# Automated_Blinds_Remote.net
KiCad netlist of a schematic drawn in EAGLE
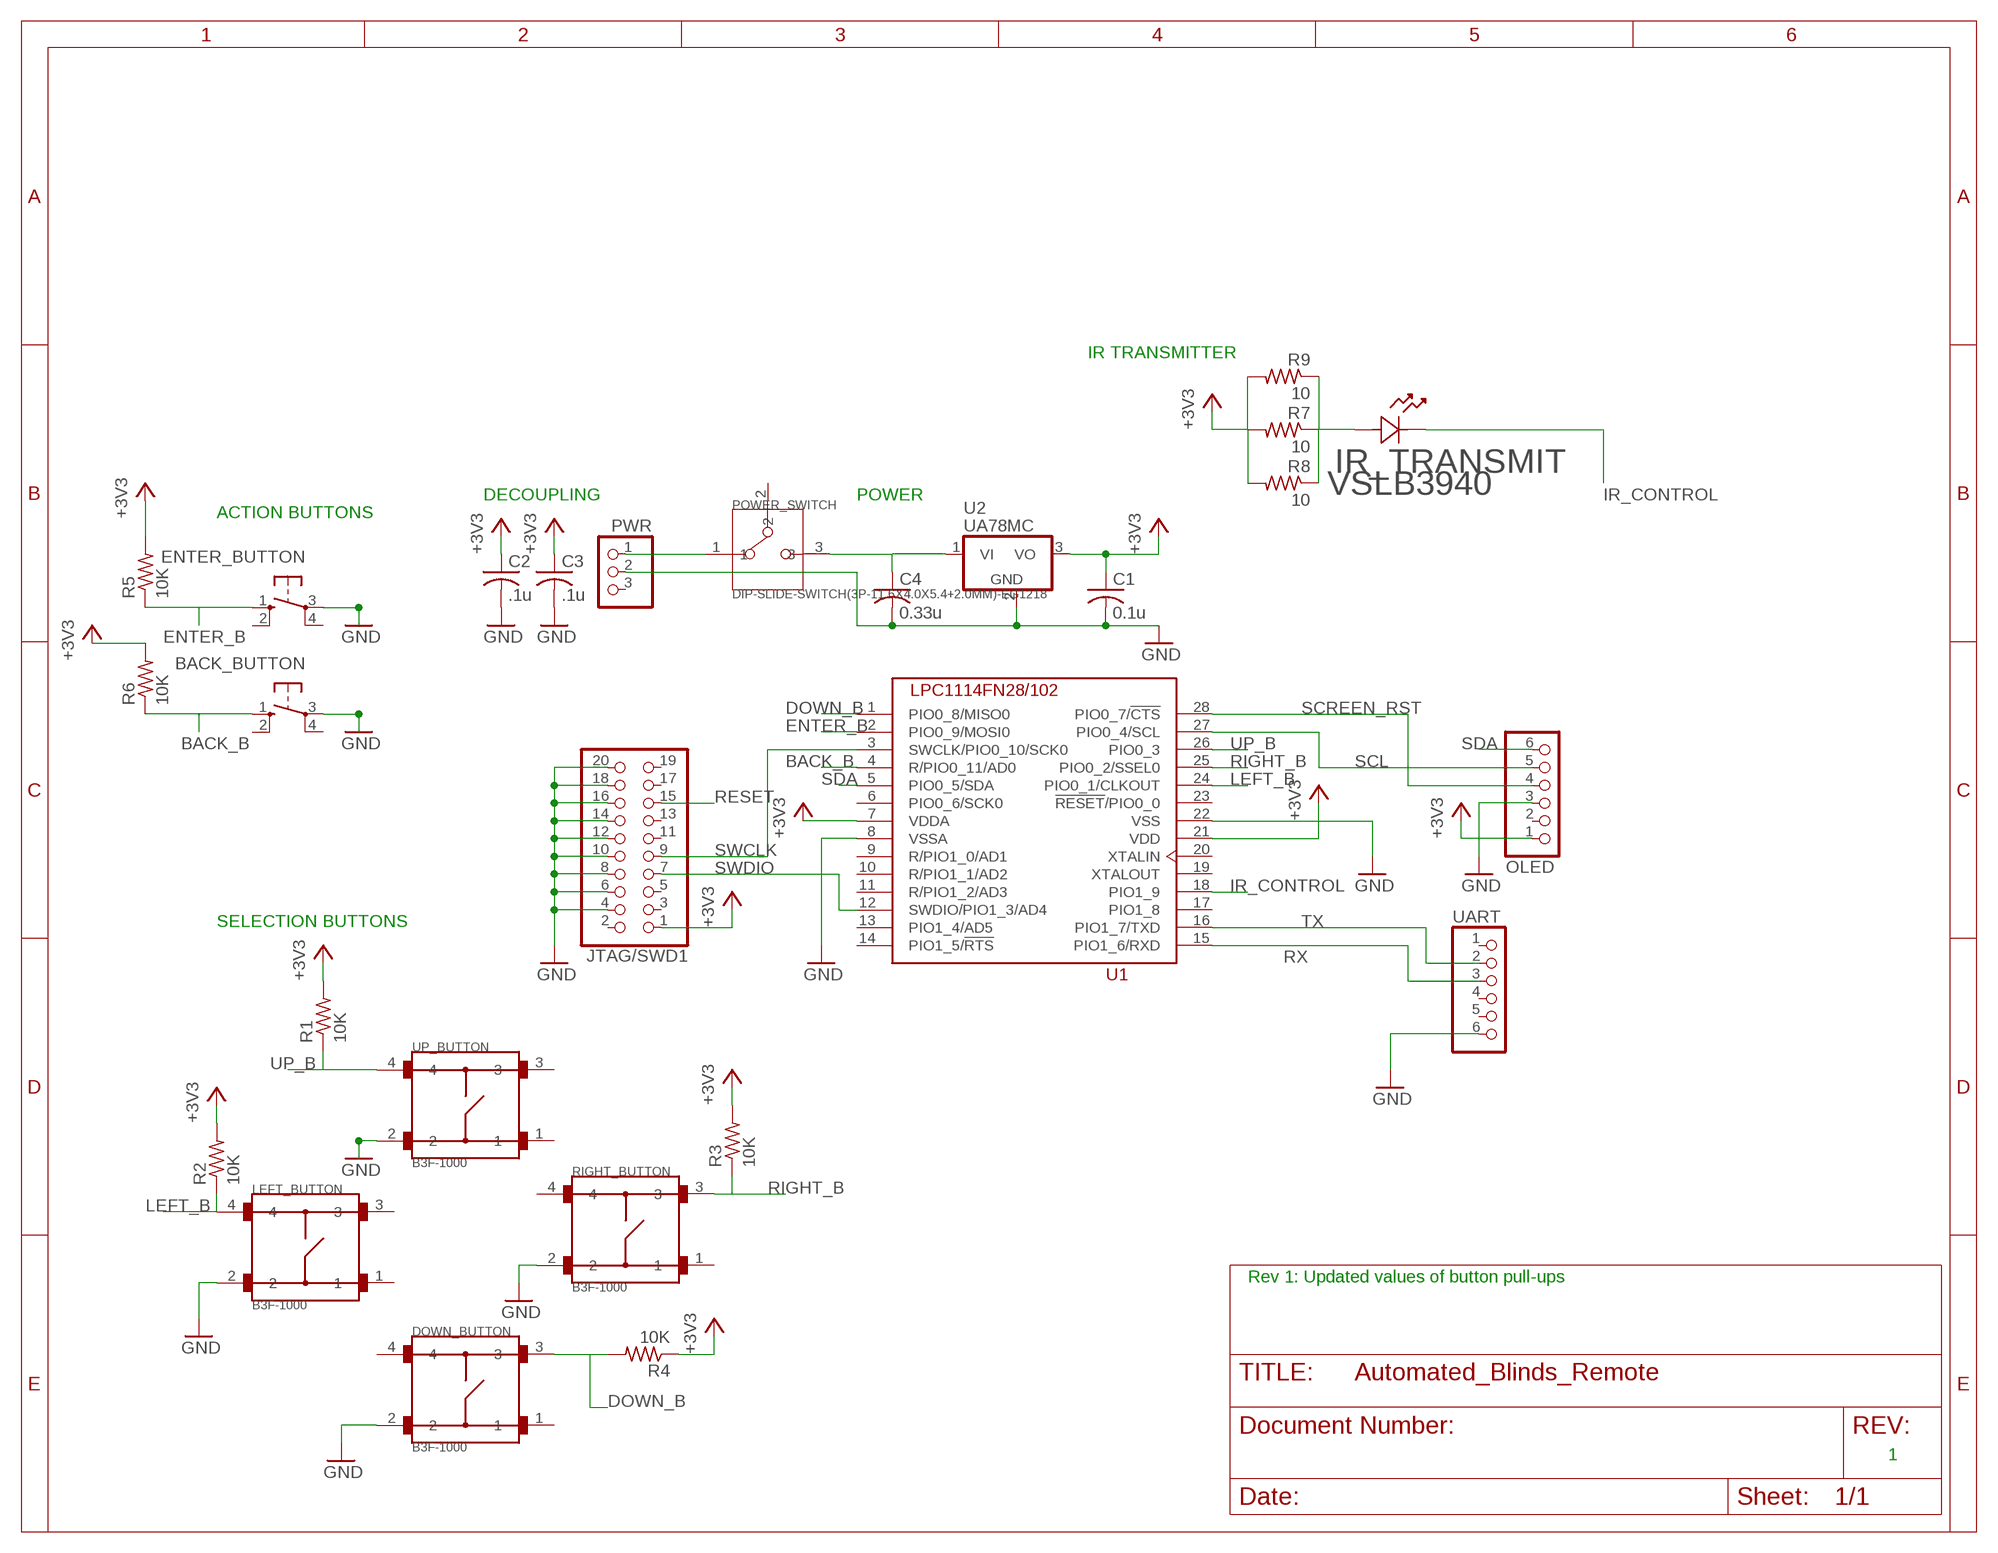
[diagram p0: schematic, sheet 1]

(export (version "E")
  (design (tool "Eeschema 10.0.6"))
  (components
    (comp (ref "BACK_BUTTON")
      (value "40/XX")
      (footprint "eagle-import:B3F_40XX")
      (libsource (lib "eagle-import") (part "40/XX"))
    )
    (comp (ref "C1")
      (value "0.1u")
      (footprint "eagle-import:C050-024X044")
      (libsource (lib "eagle-import") (part "C-US050-024X044"))
    )
    (comp (ref "C2")
      (value ".1u")
      (footprint "eagle-import:C050-024X044")
      (libsource (lib "eagle-import") (part "C-US050-024X044"))
    )
    (comp (ref "C3")
      (value ".1u")
      (footprint "eagle-import:C050-024X044")
      (libsource (lib "eagle-import") (part "C-US050-024X044"))
    )
    (comp (ref "C4")
      (value "0.33u")
      (footprint "eagle-import:C050-024X044")
      (libsource (lib "eagle-import") (part "C-US050-024X044"))
    )
    (comp (ref "DOWN_BUTTON")
      (value "B3F-1000")
      (footprint "eagle-import:SW_B3F-1000")
      (fields (field (name "MF") "Omron"))
      (libsource (lib "eagle-import") (part "B3F-1000"))
    )
    (comp (ref "ENTER_BUTTON")
      (value "40/XX")
      (footprint "eagle-import:B3F_40XX")
      (libsource (lib "eagle-import") (part "40/XX"))
    )
    (comp (ref "IR_TRANSMIT")
      (value "VSLB3940")
      (footprint "eagle-import:LED_TLH")
      (libsource (lib "eagle-import") (part "VSLB3940"))
    )
    (comp (ref "JTAG/SWD1")
      (value "PINHD-2X10")
      (footprint "eagle-import:2X10")
      (libsource (lib "eagle-import") (part "PINHD-2X10"))
    )
    (comp (ref "LEFT_BUTTON")
      (value "B3F-1000")
      (footprint "eagle-import:SW_B3F-1000")
      (fields (field (name "MF") "Omron"))
      (libsource (lib "eagle-import") (part "B3F-1000"))
    )
    (comp (ref "OLED")
      (value "PINHD-1X6")
      (footprint "eagle-import:1X06")
      (libsource (lib "eagle-import") (part "PINHD-1X6"))
    )
    (comp (ref "POWER_SWITCH")
      (value "DIP-SLIDE-SWITCH(3P-11.6X4.0X5.4+2.0MM)-EG1218")
      (footprint "eagle-import:SW3-2.5-11.6X4.0X5.4+2.0MM")
      (fields (field (name "MF") "E-Switch") (field (name "MP") "EG1218"))
      (libsource (lib "eagle-import") (part "DIP-SLIDE-SWITCH(3P-11.6X4.0X5.4+2.0MM)-EG1218"))
    )
    (comp (ref "PWR")
      (value "PINHD-1X3")
      (footprint "eagle-import:1X03")
      (libsource (lib "eagle-import") (part "PINHD-1X3"))
    )
    (comp (ref "R1")
      (value "10K")
      (footprint "eagle-import:0207_10")
      (libsource (lib "eagle-import") (part "R-US_0207/10"))
    )
    (comp (ref "R2")
      (value "10K")
      (footprint "eagle-import:0207_10")
      (libsource (lib "eagle-import") (part "R-US_0207/10"))
    )
    (comp (ref "R3")
      (value "10K")
      (footprint "eagle-import:0207_10")
      (libsource (lib "eagle-import") (part "R-US_0207/10"))
    )
    (comp (ref "R4")
      (value "10K")
      (footprint "eagle-import:0207_10")
      (libsource (lib "eagle-import") (part "R-US_0207/10"))
    )
    (comp (ref "R5")
      (value "10K")
      (footprint "eagle-import:0207_10")
      (libsource (lib "eagle-import") (part "R-US_0207/10"))
    )
    (comp (ref "R6")
      (value "10K")
      (footprint "eagle-import:0207_10")
      (libsource (lib "eagle-import") (part "R-US_0207/10"))
    )
    (comp (ref "R7")
      (value "10")
      (footprint "eagle-import:0207_10")
      (libsource (lib "eagle-import") (part "R-US_0207/10"))
    )
    (comp (ref "R8")
      (value "10")
      (footprint "eagle-import:0207_10")
      (libsource (lib "eagle-import") (part "R-US_0207/10"))
    )
    (comp (ref "R9")
      (value "10")
      (footprint "eagle-import:0207_10")
      (libsource (lib "eagle-import") (part "R-US_0207/10"))
    )
    (comp (ref "RIGHT_BUTTON")
      (value "B3F-1000")
      (footprint "eagle-import:SW_B3F-1000")
      (fields (field (name "MF") "Omron"))
      (libsource (lib "eagle-import") (part "B3F-1000"))
    )
    (comp (ref "U1")
      (value "LPC1114FN28/102")
      (footprint "eagle-import:DIL28-6")
      (libsource (lib "eagle-import") (part "LPC1114FN28/102"))
    )
    (comp (ref "U2")
      (value "UA78MC")
      (footprint "eagle-import:TO220V")
      (libsource (lib "eagle-import") (part "UA78MC"))
    )
    (comp (ref "UART")
      (value "PINHD-1X6")
      (footprint "eagle-import:1X06")
      (libsource (lib "eagle-import") (part "PINHD-1X6"))
    )
    (comp (ref "UP_BUTTON")
      (value "B3F-1000")
      (footprint "eagle-import:SW_B3F-1000")
      (fields (field (name "MF") "Omron"))
      (libsource (lib "eagle-import") (part "B3F-1000"))
    )
  )
  (nets
    (net (code "1") (name "+3V3") (class "Default")
      (node (ref "C1") (pin "1") (pinfunction "1_1") (pintype "passive"))
      (node (ref "C2") (pin "1") (pinfunction "1_1") (pintype "passive"))
      (node (ref "C3") (pin "1") (pinfunction "1_1") (pintype "passive"))
      (node (ref "JTAG/SWD1") (pin "1") (pinfunction "1_1") (pintype "passive"))
      (node (ref "OLED") (pin "1") (pinfunction "1_1") (pintype "passive"))
      (node (ref "R1") (pin "2") (pinfunction "2_2") (pintype "passive"))
      (node (ref "R2") (pin "2") (pinfunction "2_2") (pintype "passive"))
      (node (ref "R3") (pin "2") (pinfunction "2_2") (pintype "passive"))
      (node (ref "R4") (pin "1") (pinfunction "1_1") (pintype "passive"))
      (node (ref "R5") (pin "2") (pinfunction "2_2") (pintype "passive"))
      (node (ref "R6") (pin "2") (pinfunction "2_2") (pintype "passive"))
      (node (ref "R7") (pin "2") (pinfunction "2_2") (pintype "passive"))
      (node (ref "R8") (pin "2") (pinfunction "2_2") (pintype "passive"))
      (node (ref "R9") (pin "2") (pinfunction "2_2") (pintype "passive"))
      (node (ref "U1") (pin "21") (pinfunction "VDD_21") (pintype "power_in"))
      (node (ref "U1") (pin "7") (pinfunction "VDDA_7") (pintype "power_in"))
      (node (ref "U2") (pin "3") (pinfunction "VO_3") (pintype "passive"))
    )
    (net (code "2") (name "/BACK_B") (class "Default")
      (node (ref "BACK_BUTTON") (pin "1") (pinfunction "S_1") (pintype "passive"))
      (node (ref "R6") (pin "1") (pinfunction "1_1") (pintype "passive"))
      (node (ref "U1") (pin "4") (pinfunction "R/PIO0_11/AD0_4") (pintype "bidirectional"))
    )
    (net (code "3") (name "/DOWN_B") (class "Default")
      (node (ref "DOWN_BUTTON") (pin "3") (pinfunction "3_3") (pintype "passive"))
      (node (ref "R4") (pin "2") (pinfunction "2_2") (pintype "passive"))
      (node (ref "U1") (pin "1") (pinfunction "PIO0_8/MISO0_1") (pintype "bidirectional"))
    )
    (net (code "4") (name "/ENTER_B") (class "Default")
      (node (ref "ENTER_BUTTON") (pin "1") (pinfunction "S_1") (pintype "passive"))
      (node (ref "R5") (pin "1") (pinfunction "1_1") (pintype "passive"))
      (node (ref "U1") (pin "2") (pinfunction "PIO0_9/MOSI0_2") (pintype "bidirectional"))
    )
    (net (code "5") (name "/IR_CONTROL") (class "Default")
      (node (ref "IR_TRANSMIT") (pin "1") (pinfunction "11_1") (pintype "passive"))
      (node (ref "U1") (pin "18") (pinfunction "PIO1_9_18") (pintype "bidirectional"))
    )
    (net (code "6") (name "/LEFT_B") (class "Default")
      (node (ref "LEFT_BUTTON") (pin "4") (pinfunction "4_4") (pintype "passive"))
      (node (ref "R2") (pin "1") (pinfunction "1_1") (pintype "passive"))
      (node (ref "U1") (pin "24") (pinfunction "PIO0_1/CLKOUT_24") (pintype "bidirectional"))
    )
    (net (code "7") (name "/RESET") (class "Default")
      (node (ref "JTAG/SWD1") (pin "15") (pinfunction "15_15") (pintype "passive"))
    )
    (net (code "8") (name "/RIGHT_B") (class "Default")
      (node (ref "R3") (pin "1") (pinfunction "1_1") (pintype "passive"))
      (node (ref "RIGHT_BUTTON") (pin "3") (pinfunction "3_3") (pintype "passive"))
      (node (ref "U1") (pin "25") (pinfunction "PIO0_2/SSEL0_25") (pintype "bidirectional"))
    )
    (net (code "9") (name "/RX") (class "Default")
      (node (ref "U1") (pin "15") (pinfunction "PIO1_6/RXD_15") (pintype "bidirectional"))
      (node (ref "UART") (pin "3") (pinfunction "3_3") (pintype "passive"))
    )
    (net (code "10") (name "/SCL") (class "Default")
      (node (ref "OLED") (pin "5") (pinfunction "5_5") (pintype "passive"))
      (node (ref "U1") (pin "27") (pinfunction "PIO0_4/SCL_27") (pintype "bidirectional"))
    )
    (net (code "11") (name "/SCREEN_RST") (class "Default")
      (node (ref "OLED") (pin "4") (pinfunction "4_4") (pintype "passive"))
      (node (ref "U1") (pin "28") (pinfunction "PIO0_7/~{CTS}_28") (pintype "bidirectional"))
    )
    (net (code "12") (name "/SDA") (class "Default")
      (node (ref "OLED") (pin "6") (pinfunction "6_6") (pintype "passive"))
      (node (ref "U1") (pin "5") (pinfunction "PIO0_5/SDA_5") (pintype "bidirectional"))
    )
    (net (code "13") (name "/SWCLK") (class "Default")
      (node (ref "JTAG/SWD1") (pin "9") (pinfunction "9_9") (pintype "passive"))
      (node (ref "U1") (pin "3") (pinfunction "SWCLK/PIO0_10/SCK0_3") (pintype "bidirectional"))
    )
    (net (code "14") (name "/SWDIO") (class "Default")
      (node (ref "JTAG/SWD1") (pin "7") (pinfunction "7_7") (pintype "passive"))
      (node (ref "U1") (pin "12") (pinfunction "SWDIO/PIO1_3/AD4_12") (pintype "bidirectional"))
    )
    (net (code "15") (name "/TX") (class "Default")
      (node (ref "U1") (pin "16") (pinfunction "PIO1_7/TXD_16") (pintype "bidirectional"))
      (node (ref "UART") (pin "2") (pinfunction "2_2") (pintype "passive"))
    )
    (net (code "16") (name "/UP_B") (class "Default")
      (node (ref "R1") (pin "1") (pinfunction "1_1") (pintype "passive"))
      (node (ref "U1") (pin "26") (pinfunction "PIO0_3_26") (pintype "bidirectional"))
      (node (ref "UP_BUTTON") (pin "4") (pinfunction "4_4") (pintype "passive"))
    )
    (net (code "17") (name "GND") (class "Default")
      (node (ref "BACK_BUTTON") (pin "3") (pinfunction "P_3") (pintype "passive"))
      (node (ref "C1") (pin "2") (pinfunction "2_2") (pintype "passive"))
      (node (ref "C2") (pin "2") (pinfunction "2_2") (pintype "passive"))
      (node (ref "C3") (pin "2") (pinfunction "2_2") (pintype "passive"))
      (node (ref "C4") (pin "2") (pinfunction "2_2") (pintype "passive"))
      (node (ref "DOWN_BUTTON") (pin "2") (pinfunction "2_2") (pintype "passive"))
      (node (ref "ENTER_BUTTON") (pin "3") (pinfunction "P_3") (pintype "passive"))
      (node (ref "JTAG/SWD1") (pin "10") (pinfunction "10_10") (pintype "passive"))
      (node (ref "JTAG/SWD1") (pin "12") (pinfunction "12_12") (pintype "passive"))
      (node (ref "JTAG/SWD1") (pin "14") (pinfunction "14_14") (pintype "passive"))
      (node (ref "JTAG/SWD1") (pin "16") (pinfunction "16_16") (pintype "passive"))
      (node (ref "JTAG/SWD1") (pin "18") (pinfunction "18_18") (pintype "passive"))
      (node (ref "JTAG/SWD1") (pin "20") (pinfunction "20_20") (pintype "passive"))
      (node (ref "JTAG/SWD1") (pin "4") (pinfunction "4_4") (pintype "passive"))
      (node (ref "JTAG/SWD1") (pin "6") (pinfunction "6_6") (pintype "passive"))
      (node (ref "JTAG/SWD1") (pin "8") (pinfunction "8_8") (pintype "passive"))
      (node (ref "LEFT_BUTTON") (pin "2") (pinfunction "2_2") (pintype "passive"))
      (node (ref "OLED") (pin "3") (pinfunction "3_3") (pintype "passive"))
      (node (ref "PWR") (pin "2") (pinfunction "2_2") (pintype "passive"))
      (node (ref "RIGHT_BUTTON") (pin "2") (pinfunction "2_2") (pintype "passive"))
      (node (ref "U1") (pin "22") (pinfunction "VSS_22") (pintype "power_in"))
      (node (ref "U1") (pin "8") (pinfunction "VSSA_8") (pintype "power_in"))
      (node (ref "U2") (pin "2") (pinfunction "GND_2") (pintype "passive"))
      (node (ref "UART") (pin "6") (pinfunction "6_6") (pintype "passive"))
      (node (ref "UP_BUTTON") (pin "2") (pinfunction "2_2") (pintype "passive"))
    )
    (net (code "18") (name "Net-(IR_TRANSMIT-22)") (class "Default")
      (node (ref "IR_TRANSMIT") (pin "2") (pinfunction "22_2") (pintype "passive"))
      (node (ref "R7") (pin "1") (pinfunction "1_1") (pintype "passive"))
      (node (ref "R8") (pin "1") (pinfunction "1_1") (pintype "passive"))
      (node (ref "R9") (pin "1") (pinfunction "1_1") (pintype "passive"))
    )
    (net (code "19") (name "Net-(POWER_SWITCH-Pad1)") (class "Default")
      (node (ref "POWER_SWITCH") (pin "1") (pinfunction "1_1") (pintype "bidirectional"))
      (node (ref "PWR") (pin "1") (pinfunction "1_1") (pintype "passive"))
    )
    (net (code "20") (name "Net-(U2-VI)") (class "Default")
      (node (ref "C4") (pin "1") (pinfunction "1_1") (pintype "passive"))
      (node (ref "POWER_SWITCH") (pin "3") (pinfunction "3_3") (pintype "bidirectional"))
      (node (ref "U2") (pin "1") (pinfunction "VI_1") (pintype "input"))
    )
    (net (code "21") (name "unconnected-(BACK_BUTTON-P1-Pad4)") (class "Default")
      (node (ref "BACK_BUTTON") (pin "4") (pinfunction "P1_4") (pintype "passive"))
    )
    (net (code "22") (name "unconnected-(BACK_BUTTON-S1-Pad2)") (class "Default")
      (node (ref "BACK_BUTTON") (pin "2") (pinfunction "S1_2") (pintype "passive"))
    )
    (net (code "23") (name "unconnected-(DOWN_BUTTON-Pad1)") (class "Default")
      (node (ref "DOWN_BUTTON") (pin "1") (pinfunction "1_1") (pintype "passive"))
    )
    (net (code "24") (name "unconnected-(DOWN_BUTTON-Pad4)") (class "Default")
      (node (ref "DOWN_BUTTON") (pin "4") (pinfunction "4_4") (pintype "passive"))
    )
    (net (code "25") (name "unconnected-(ENTER_BUTTON-P1-Pad4)") (class "Default")
      (node (ref "ENTER_BUTTON") (pin "4") (pinfunction "P1_4") (pintype "passive"))
    )
    (net (code "26") (name "unconnected-(ENTER_BUTTON-S1-Pad2)") (class "Default")
      (node (ref "ENTER_BUTTON") (pin "2") (pinfunction "S1_2") (pintype "passive"))
    )
    (net (code "27") (name "unconnected-(JTAG/SWD1-Pad2)") (class "Default")
      (node (ref "JTAG/SWD1") (pin "2") (pinfunction "2_2") (pintype "passive"))
    )
    (net (code "28") (name "unconnected-(JTAG/SWD1-Pad3)") (class "Default")
      (node (ref "JTAG/SWD1") (pin "3") (pinfunction "3_3") (pintype "passive"))
    )
    (net (code "29") (name "unconnected-(JTAG/SWD1-Pad5)") (class "Default")
      (node (ref "JTAG/SWD1") (pin "5") (pinfunction "5_5") (pintype "passive"))
    )
    (net (code "30") (name "unconnected-(JTAG/SWD1-Pad11)") (class "Default")
      (node (ref "JTAG/SWD1") (pin "11") (pinfunction "11_11") (pintype "passive"))
    )
    (net (code "31") (name "unconnected-(JTAG/SWD1-Pad13)") (class "Default")
      (node (ref "JTAG/SWD1") (pin "13") (pinfunction "13_13") (pintype "passive"))
    )
    (net (code "32") (name "unconnected-(JTAG/SWD1-Pad17)") (class "Default")
      (node (ref "JTAG/SWD1") (pin "17") (pinfunction "17_17") (pintype "passive"))
    )
    (net (code "33") (name "unconnected-(JTAG/SWD1-Pad19)") (class "Default")
      (node (ref "JTAG/SWD1") (pin "19") (pinfunction "19_19") (pintype "passive"))
    )
    (net (code "34") (name "unconnected-(LEFT_BUTTON-Pad1)") (class "Default")
      (node (ref "LEFT_BUTTON") (pin "1") (pinfunction "1_1") (pintype "passive"))
    )
    (net (code "35") (name "unconnected-(LEFT_BUTTON-Pad3)") (class "Default")
      (node (ref "LEFT_BUTTON") (pin "3") (pinfunction "3_3") (pintype "passive"))
    )
    (net (code "36") (name "unconnected-(OLED-Pad2)") (class "Default")
      (node (ref "OLED") (pin "2") (pinfunction "2_2") (pintype "passive"))
    )
    (net (code "37") (name "unconnected-(POWER_SWITCH-Pad2)") (class "Default")
      (node (ref "POWER_SWITCH") (pin "2") (pinfunction "2_2") (pintype "bidirectional"))
    )
    (net (code "38") (name "unconnected-(PWR-Pad3)") (class "Default")
      (node (ref "PWR") (pin "3") (pinfunction "3_3") (pintype "passive"))
    )
    (net (code "39") (name "unconnected-(RIGHT_BUTTON-Pad1)") (class "Default")
      (node (ref "RIGHT_BUTTON") (pin "1") (pinfunction "1_1") (pintype "passive"))
    )
    (net (code "40") (name "unconnected-(RIGHT_BUTTON-Pad4)") (class "Default")
      (node (ref "RIGHT_BUTTON") (pin "4") (pinfunction "4_4") (pintype "passive"))
    )
    (net (code "41") (name "unconnected-(U1-PIO0_6{slash}SCK0-Pad6)") (class "Default")
      (node (ref "U1") (pin "6") (pinfunction "PIO0_6/SCK0_6") (pintype "bidirectional"))
    )
    (net (code "42") (name "unconnected-(U1-PIO1_4{slash}AD5-Pad13)") (class "Default")
      (node (ref "U1") (pin "13") (pinfunction "PIO1_4/AD5_13") (pintype "bidirectional"))
    )
    (net (code "43") (name "unconnected-(U1-PIO1_5{slash}~{RTS}-Pad14)") (class "Default")
      (node (ref "U1") (pin "14") (pinfunction "PIO1_5/~{RTS}_14") (pintype "bidirectional"))
    )
    (net (code "44") (name "unconnected-(U1-PIO1_8-Pad17)") (class "Default")
      (node (ref "U1") (pin "17") (pinfunction "PIO1_8_17") (pintype "bidirectional"))
    )
    (net (code "45") (name "unconnected-(U1-R{slash}PIO1_0{slash}AD1-Pad9)") (class "Default")
      (node (ref "U1") (pin "9") (pinfunction "R/PIO1_0/AD1_9") (pintype "bidirectional"))
    )
    (net (code "46") (name "unconnected-(U1-R{slash}PIO1_1{slash}AD2-Pad10)") (class "Default")
      (node (ref "U1") (pin "10") (pinfunction "R/PIO1_1/AD2_10") (pintype "bidirectional"))
    )
    (net (code "47") (name "unconnected-(U1-R{slash}PIO1_2{slash}AD3-Pad11)") (class "Default")
      (node (ref "U1") (pin "11") (pinfunction "R/PIO1_2/AD3_11") (pintype "bidirectional"))
    )
    (net (code "48") (name "unconnected-(U1-XTALIN-Pad20)") (class "Default")
      (node (ref "U1") (pin "20") (pinfunction "XTALIN_20") (pintype "bidirectional"))
    )
    (net (code "49") (name "unconnected-(U1-XTALOUT-Pad19)") (class "Default")
      (node (ref "U1") (pin "19") (pinfunction "XTALOUT_19") (pintype "output"))
    )
    (net (code "50") (name "unconnected-(U1-~{RESET}{slash}PIO0_0-Pad23)") (class "Default")
      (node (ref "U1") (pin "23") (pinfunction "~{RESET}/PIO0_0_23") (pintype "bidirectional"))
    )
    (net (code "51") (name "unconnected-(UART-Pad1)") (class "Default")
      (node (ref "UART") (pin "1") (pinfunction "1_1") (pintype "passive"))
    )
    (net (code "52") (name "unconnected-(UART-Pad4)") (class "Default")
      (node (ref "UART") (pin "4") (pinfunction "4_4") (pintype "passive"))
    )
    (net (code "53") (name "unconnected-(UART-Pad5)") (class "Default")
      (node (ref "UART") (pin "5") (pinfunction "5_5") (pintype "passive"))
    )
    (net (code "54") (name "unconnected-(UP_BUTTON-Pad1)") (class "Default")
      (node (ref "UP_BUTTON") (pin "1") (pinfunction "1_1") (pintype "passive"))
    )
    (net (code "55") (name "unconnected-(UP_BUTTON-Pad3)") (class "Default")
      (node (ref "UP_BUTTON") (pin "3") (pinfunction "3_3") (pintype "passive"))
    )
  )
)
